# servo_cape.net
KiCad netlist of a schematic drawn in EAGLE
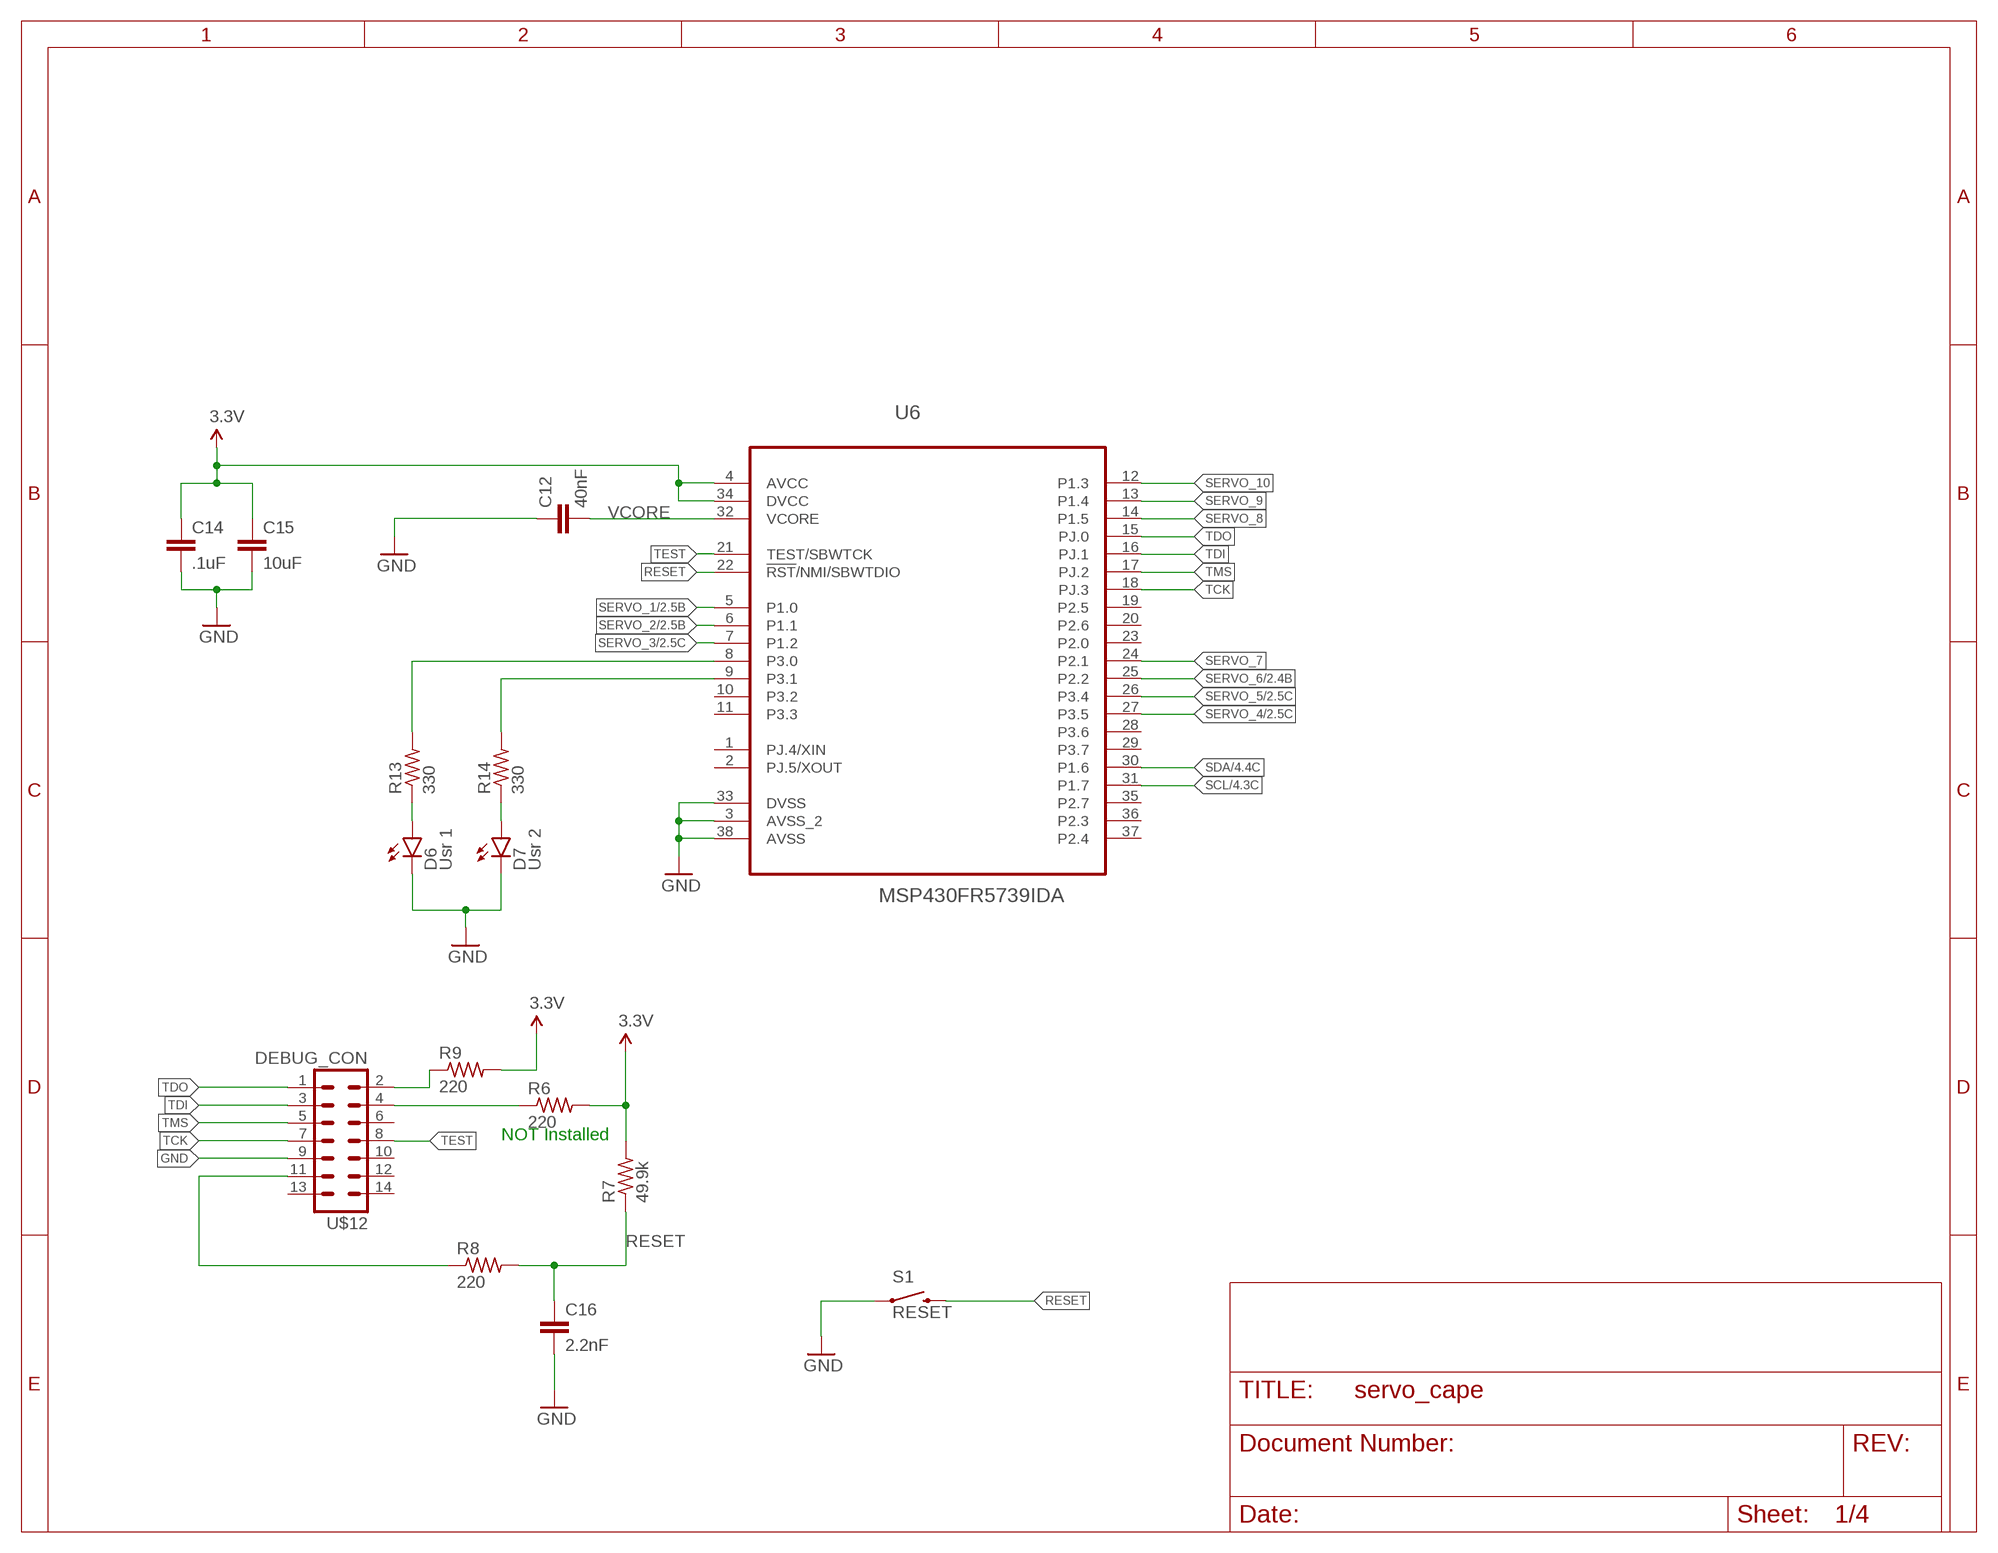
[diagram p0: schematic, sheet 1]
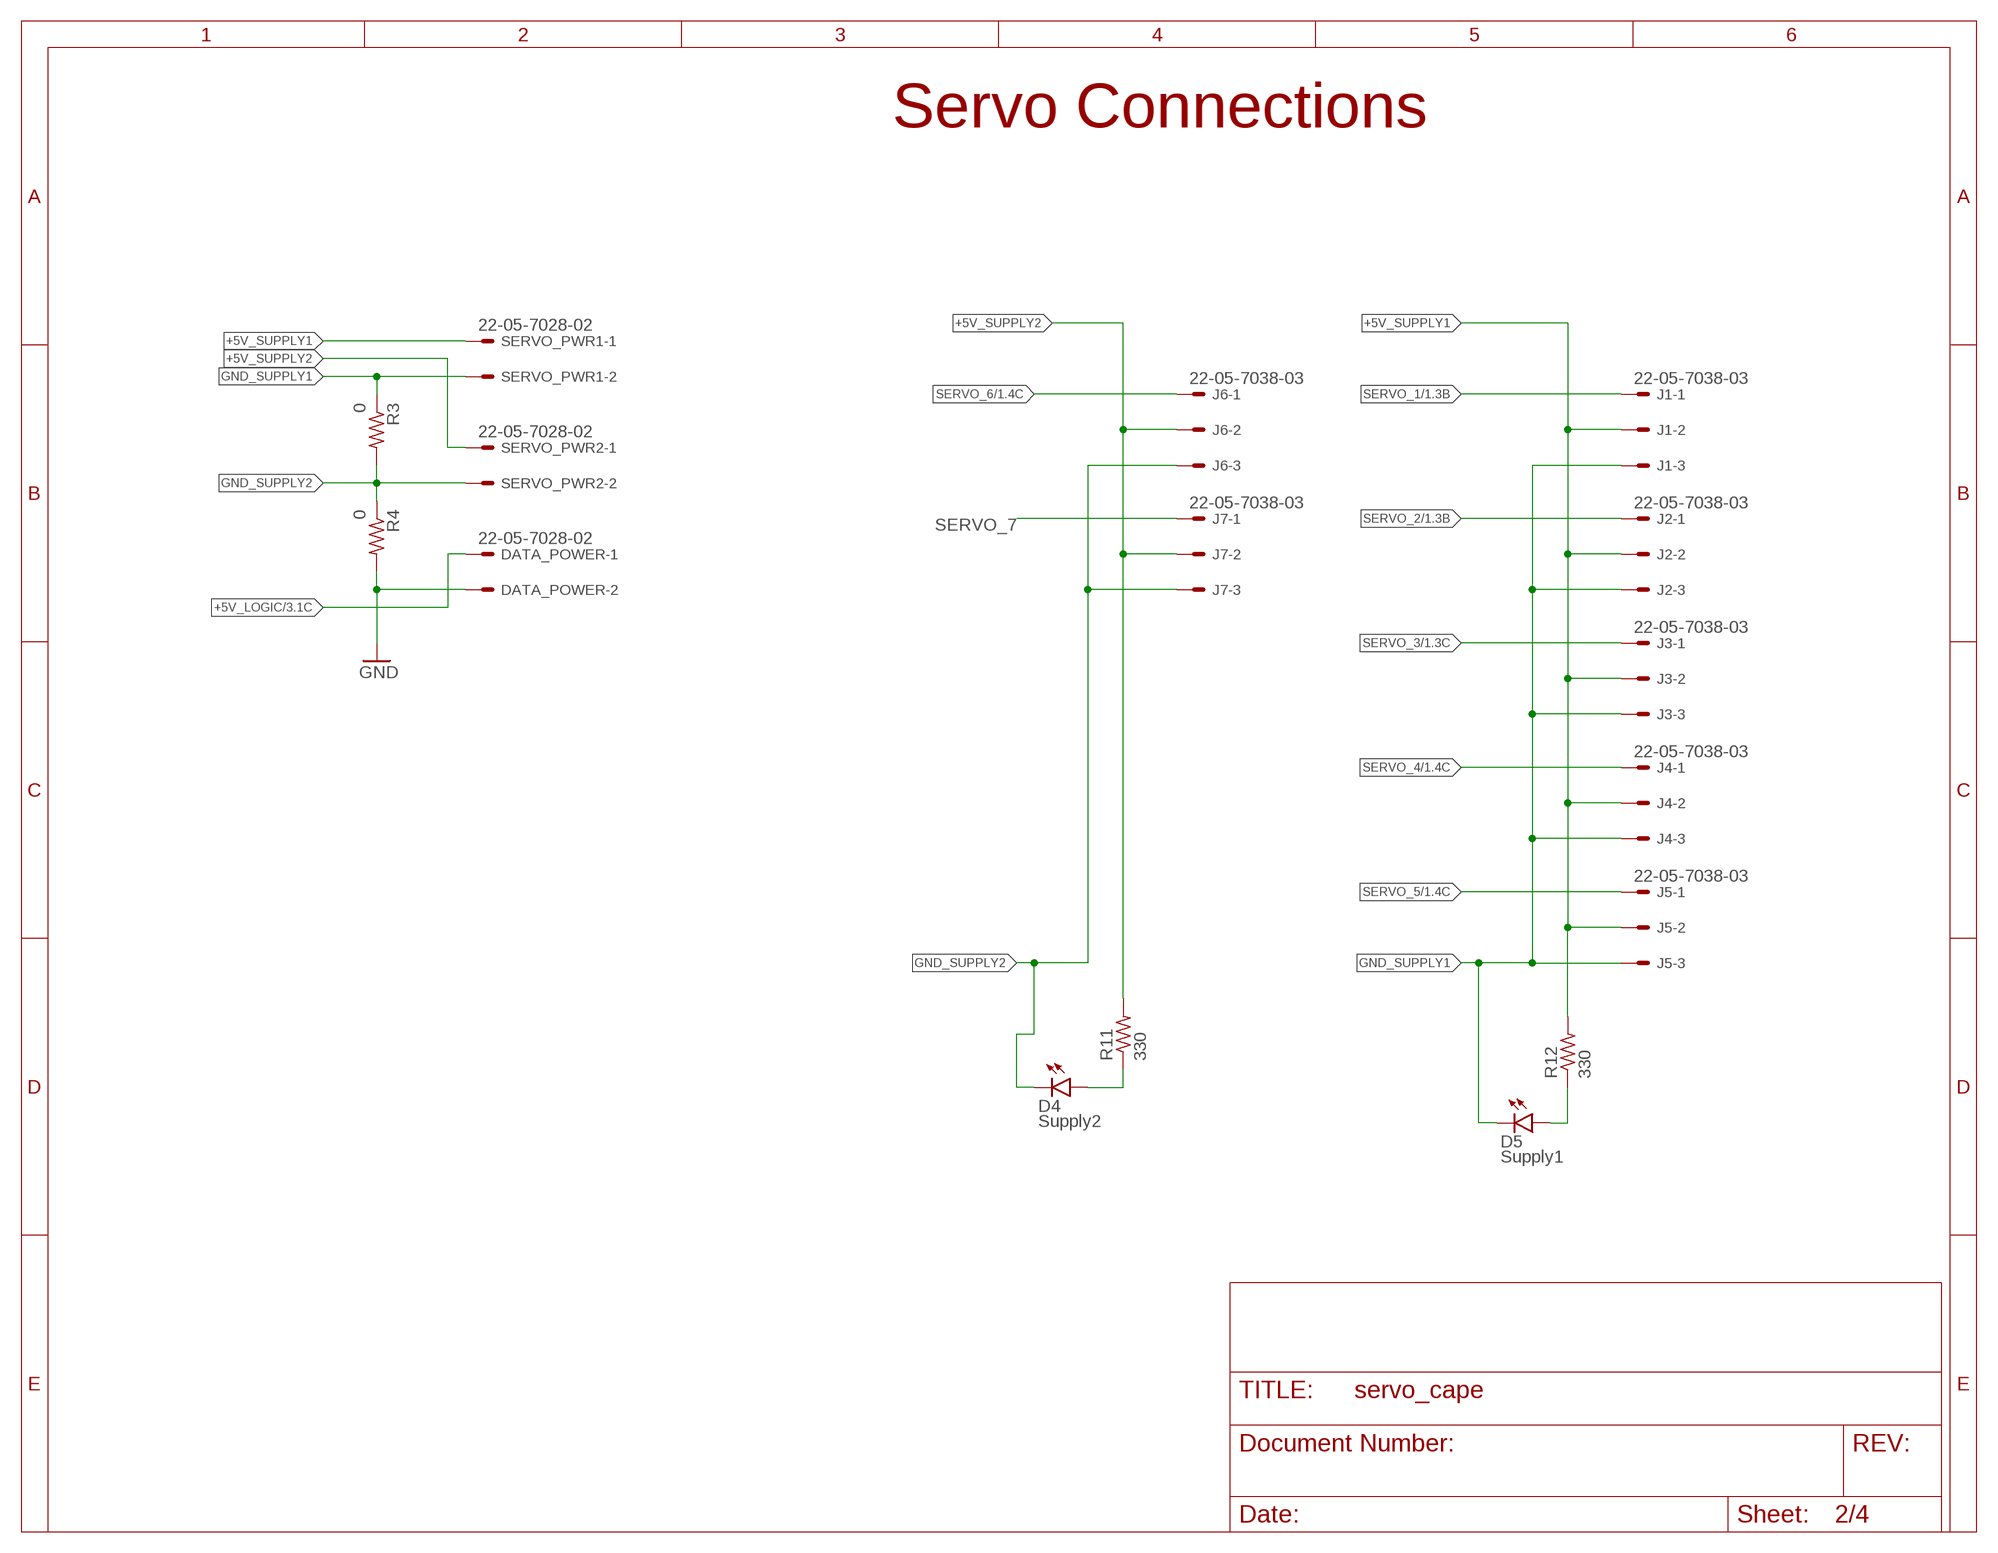
[diagram p1: schematic, sheet 2]
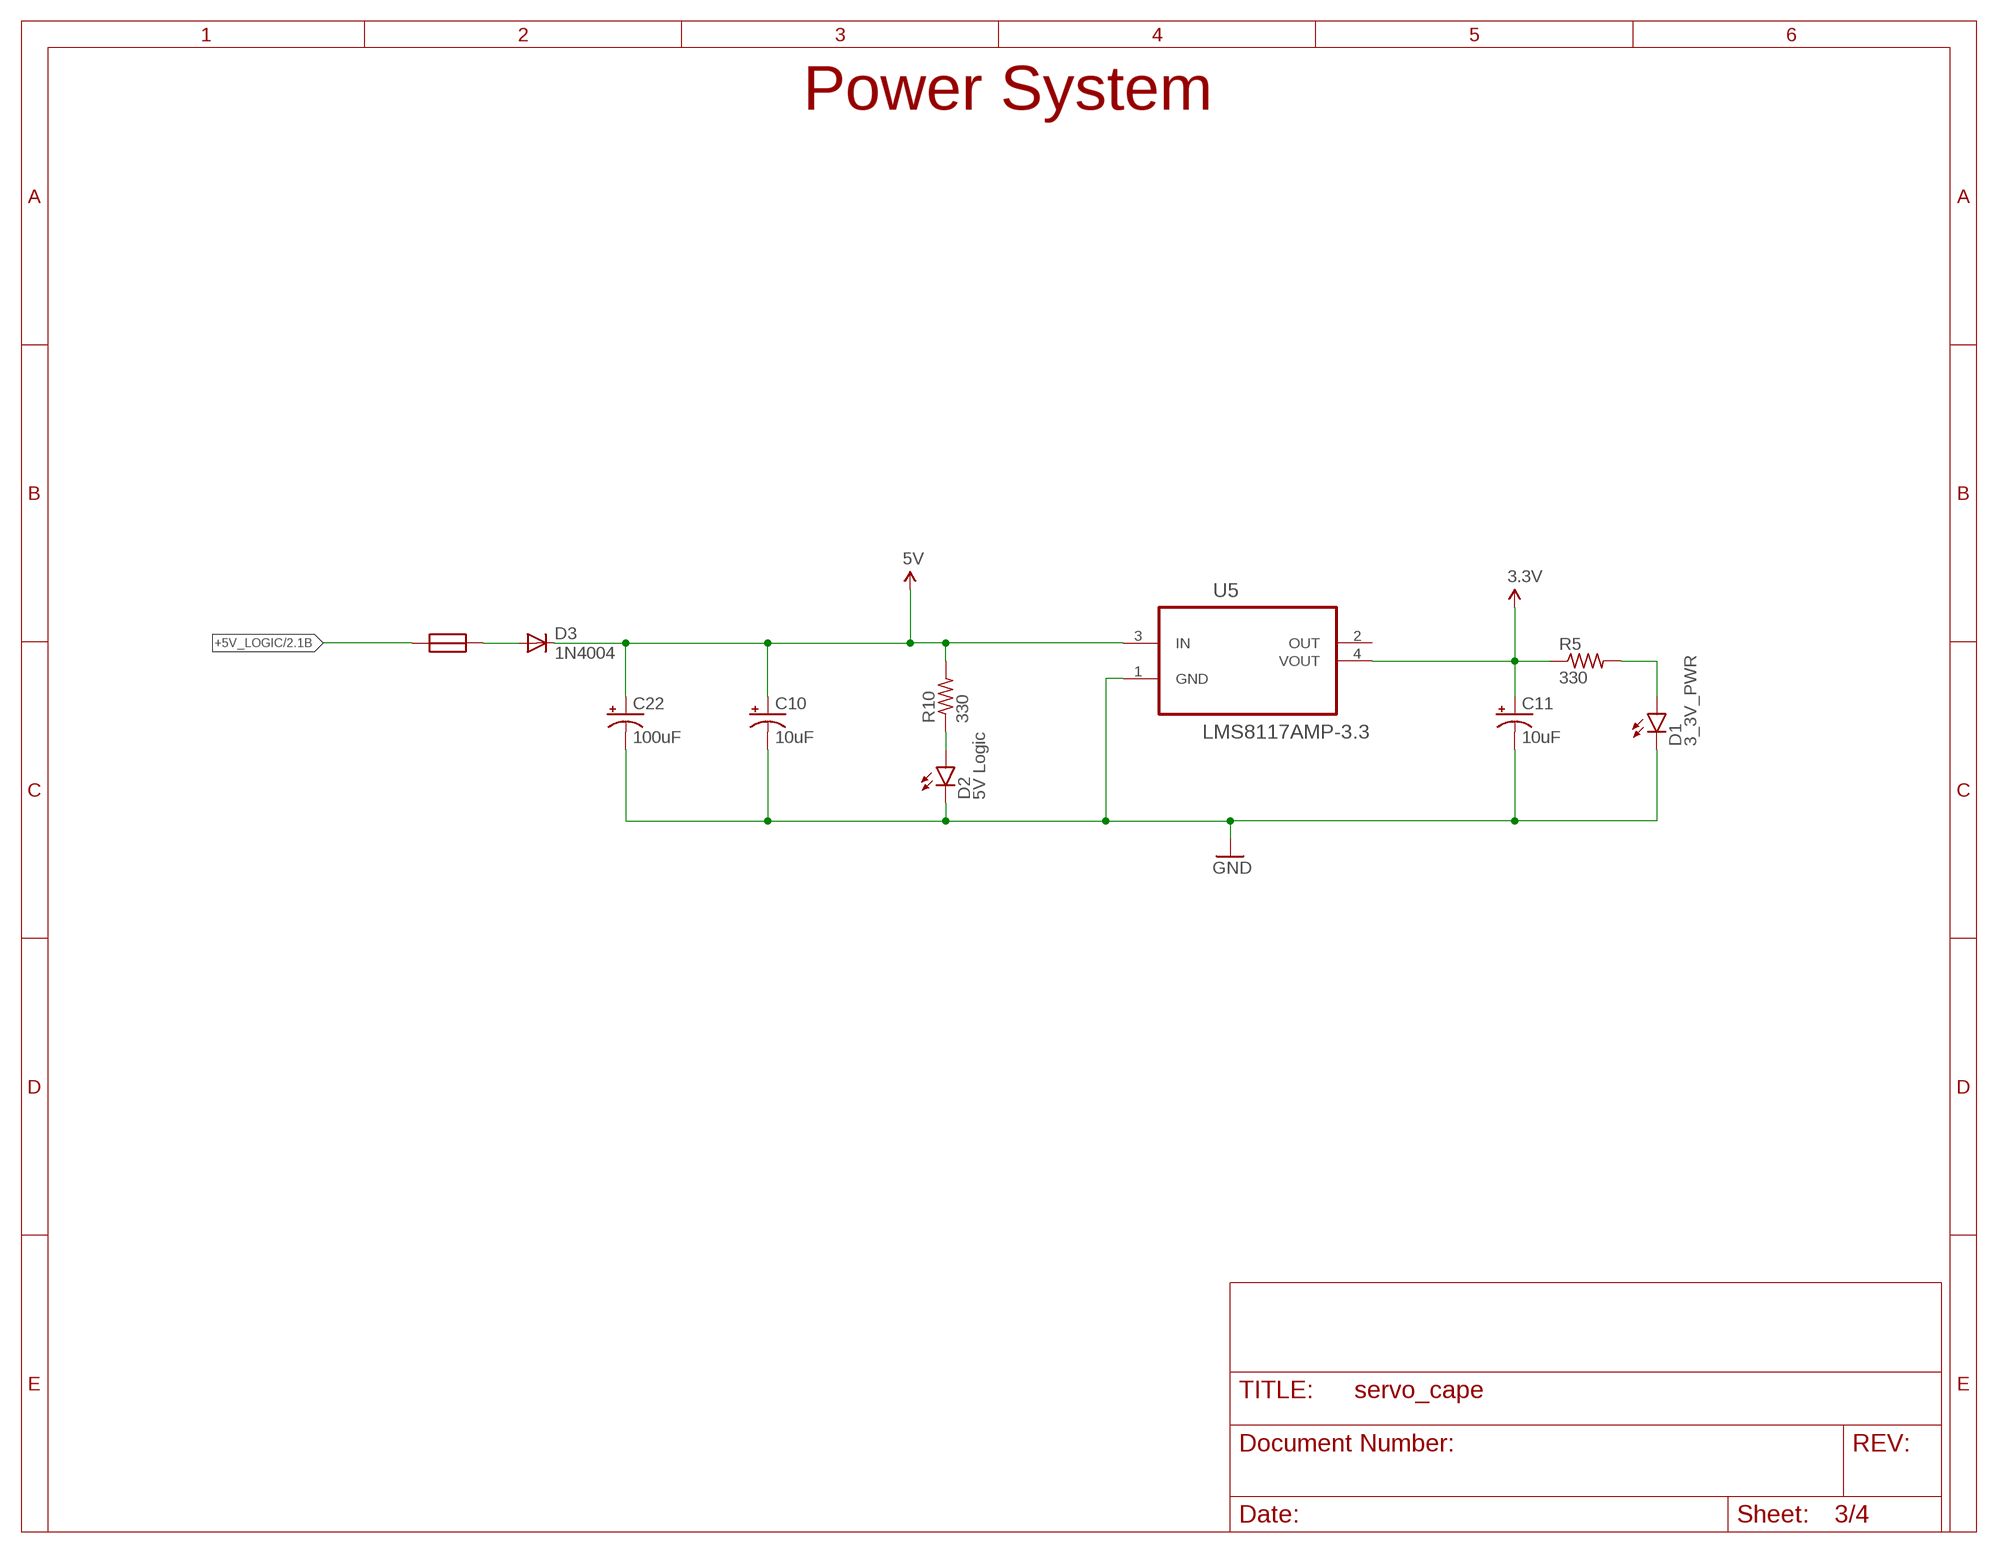
[diagram p2: schematic, sheet 3]
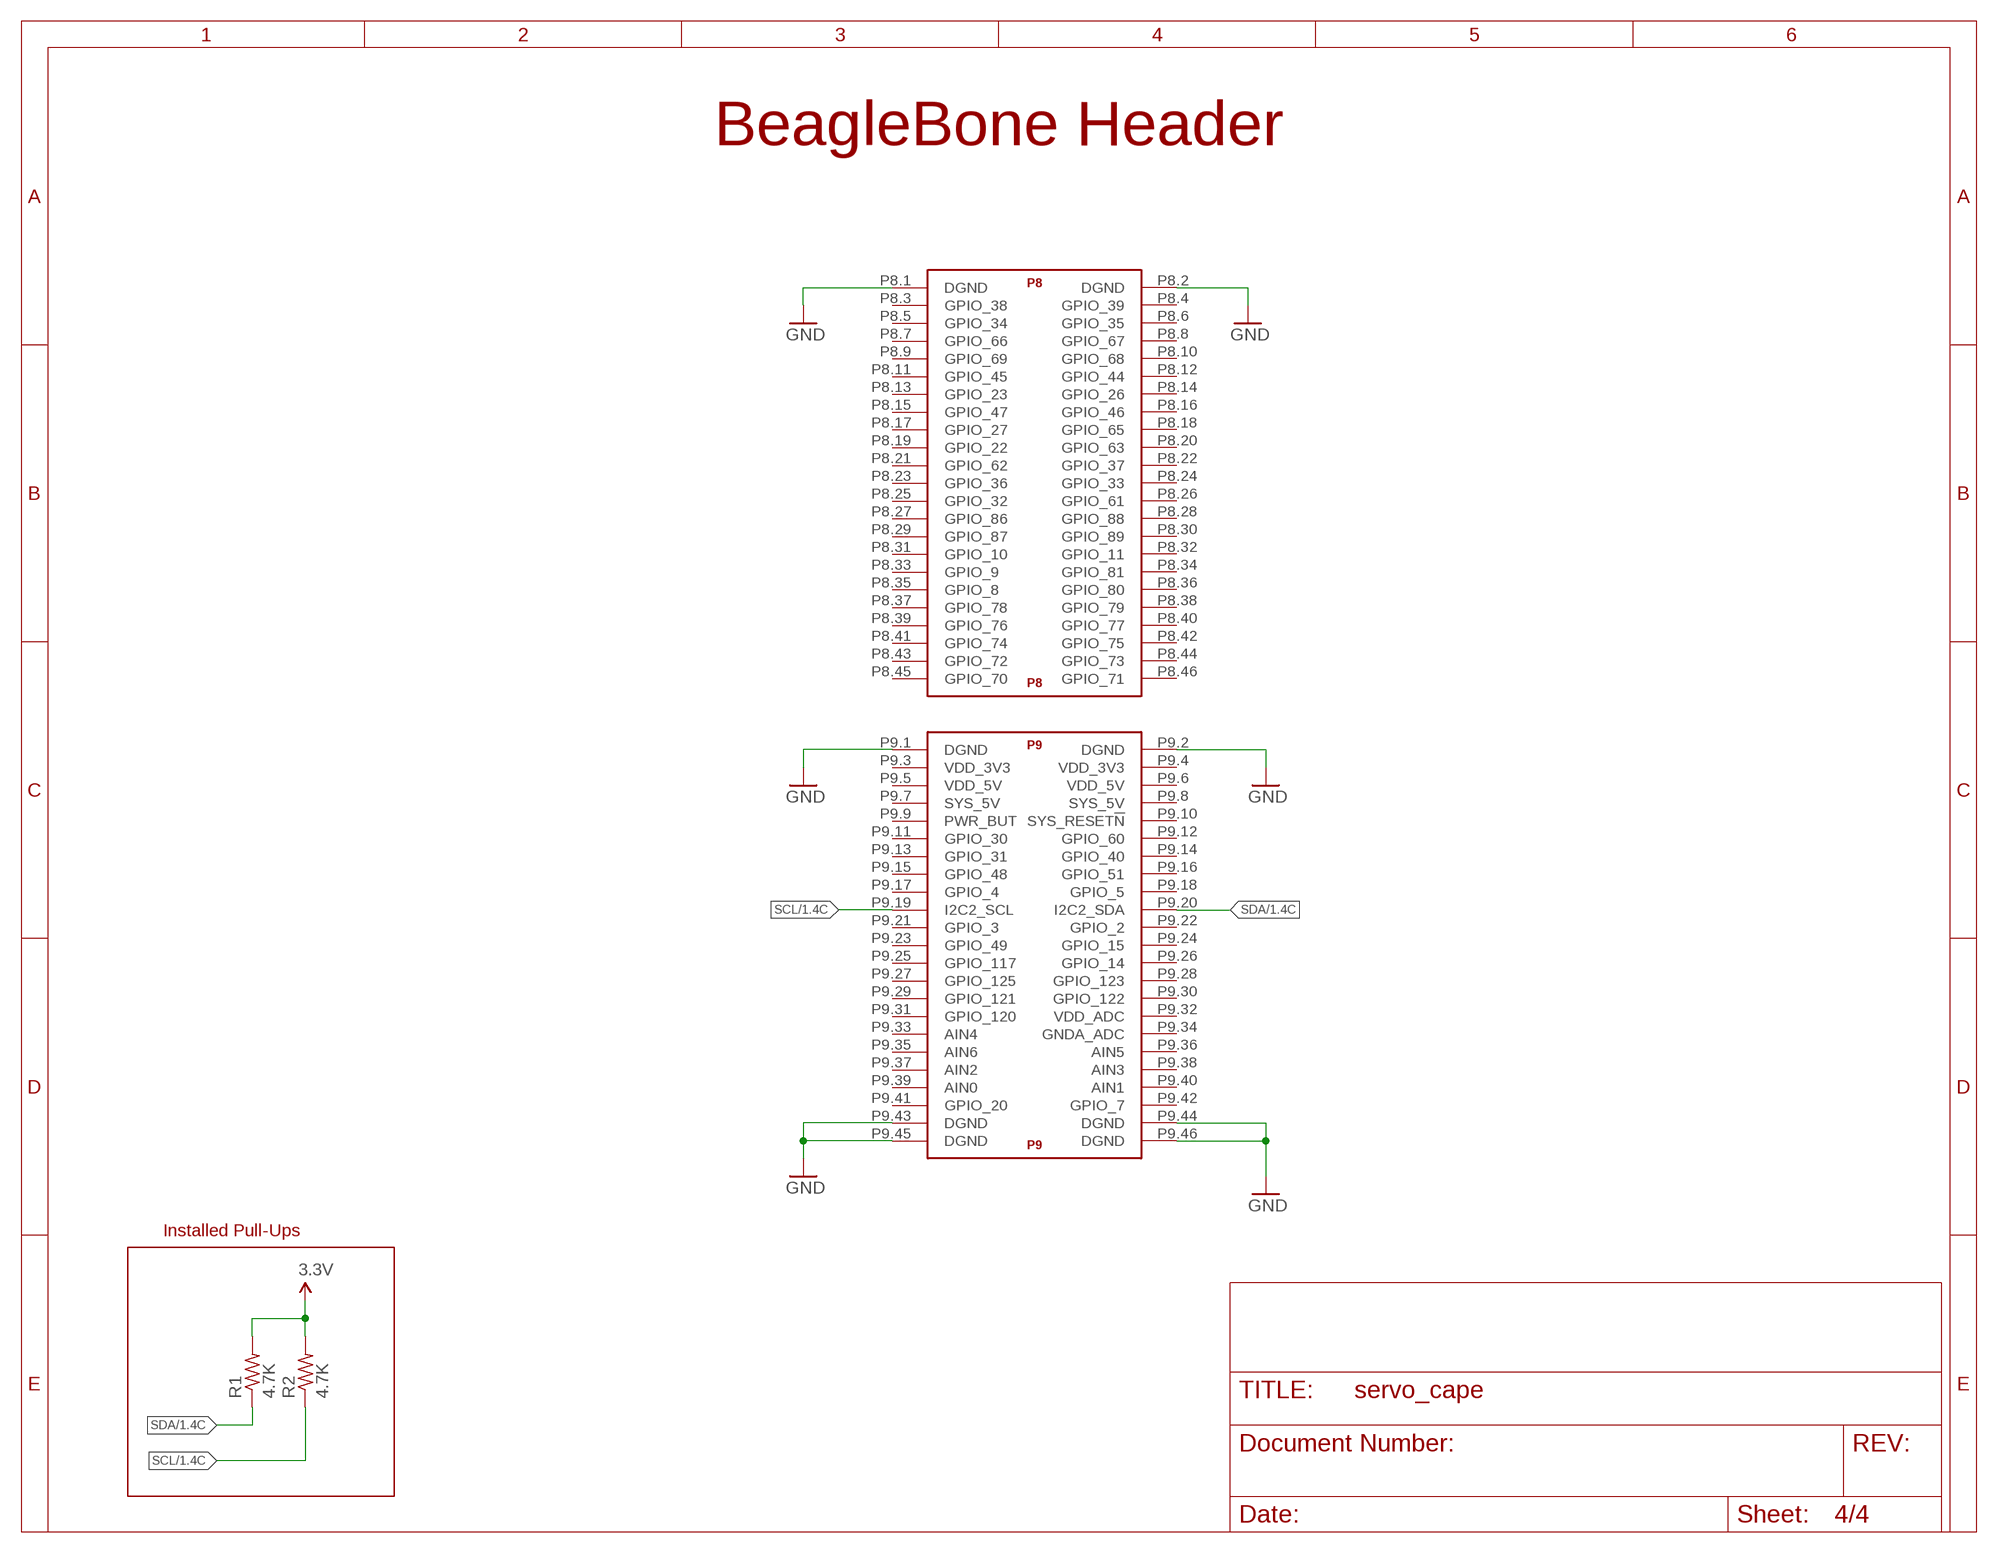
[diagram p3: schematic, sheet 4]

(export (version "E")
  (design (tool "Eeschema 10.0.6"))
  (components
    (comp (ref "D4")
      (value "Supply2")
      (footprint "eagle-import:FKIT-LED-1206")
      (libsource (lib "eagle-import") (part "LED-FKIT-1206"))
    )
    (comp (ref "D5")
      (value "Supply1")
      (footprint "eagle-import:FKIT-LED-1206")
      (libsource (lib "eagle-import") (part "LED-FKIT-1206"))
    )
    (comp (ref "DATA_POWER")
      (value "22-05-7028-02")
      (footprint "eagle-import:7395-02")
      (libsource (lib "eagle-import") (part "22-?-0205-7028"))
    )
    (comp (ref "J1")
      (value "22-05-7038-03")
      (footprint "eagle-import:7395-03")
      (libsource (lib "eagle-import") (part "22-?-0305-7038"))
    )
    (comp (ref "J2")
      (value "22-05-7038-03")
      (footprint "eagle-import:7395-03")
      (libsource (lib "eagle-import") (part "22-?-0305-7038"))
    )
    (comp (ref "J3")
      (value "22-05-7038-03")
      (footprint "eagle-import:7395-03")
      (libsource (lib "eagle-import") (part "22-?-0305-7038"))
    )
    (comp (ref "J4")
      (value "22-05-7038-03")
      (footprint "eagle-import:7395-03")
      (libsource (lib "eagle-import") (part "22-?-0305-7038"))
    )
    (comp (ref "J5")
      (value "22-05-7038-03")
      (footprint "eagle-import:7395-03")
      (libsource (lib "eagle-import") (part "22-?-0305-7038"))
    )
    (comp (ref "J6")
      (value "22-05-7038-03")
      (footprint "eagle-import:7395-03")
      (libsource (lib "eagle-import") (part "22-?-0305-7038"))
    )
    (comp (ref "J7")
      (value "22-05-7038-03")
      (footprint "eagle-import:7395-03")
      (libsource (lib "eagle-import") (part "22-?-0305-7038"))
    )
    (comp (ref "R3")
      (value "0")
      (footprint "eagle-import:R0805W")
      (libsource (lib "eagle-import") (part "R-US_R0805W"))
    )
    (comp (ref "R4")
      (value "0")
      (footprint "eagle-import:R0805W")
      (libsource (lib "eagle-import") (part "R-US_R0805W"))
    )
    (comp (ref "R11")
      (value "330")
      (footprint "eagle-import:R0805W")
      (libsource (lib "eagle-import") (part "R-US_R0805W"))
    )
    (comp (ref "R12")
      (value "330")
      (footprint "eagle-import:R0805W")
      (libsource (lib "eagle-import") (part "R-US_R0805W"))
    )
    (comp (ref "SERVO_PWR1")
      (value "22-05-7028-02")
      (footprint "eagle-import:7395-02")
      (libsource (lib "eagle-import") (part "22-?-0205-7028"))
    )
    (comp (ref "SERVO_PWR2")
      (value "22-05-7028-02")
      (footprint "eagle-import:7395-02")
      (libsource (lib "eagle-import") (part "22-?-0205-7028"))
    )
    (comp (ref "R1")
      (value "4.7K")
      (footprint "eagle-import:R0805W")
      (libsource (lib "eagle-import") (part "R-US_R0805W"))
    )
    (comp (ref "R2")
      (value "4.7K")
      (footprint "eagle-import:R0805W")
      (libsource (lib "eagle-import") (part "R-US_R0805W"))
    )
    (comp (ref "U$1")
      (value "BEAGLE_BONE_BLACK_CAPE")
      (footprint "eagle-import:BEAGLE_BONE_BLACK_CAPE")
      (libsource (lib "eagle-import") (part "BEAGLE_BONE_BLACK_CAPE"))
    )
    (comp (ref "C10")
      (value "10uF")
      (footprint "eagle-import:EIA3216")
      (libsource (lib "eagle-import") (part "10UF-16V-10%(TANT)"))
    )
    (comp (ref "C11")
      (value "10uF")
      (footprint "eagle-import:EIA3216")
      (libsource (lib "eagle-import") (part "10UF-16V-10%(TANT)"))
    )
    (comp (ref "C22")
      (value "100uF")
      (footprint "eagle-import:EIA7343")
      (libsource (lib "eagle-import") (part "100UF-10V-10%(TANT)"))
    )
    (comp (ref "D1")
      (value "3_3V_PWR")
      (footprint "eagle-import:FKIT-LED-1206")
      (libsource (lib "eagle-import") (part "LED-FKIT-1206"))
    )
    (comp (ref "D2")
      (value "5V Logic")
      (footprint "eagle-import:FKIT-LED-1206")
      (libsource (lib "eagle-import") (part "LED-FKIT-1206"))
    )
    (comp (ref "D3")
      (value "1N4004")
      (footprint "eagle-import:DO41-10")
      (libsource (lib "eagle-import") (part "1N4004"))
    )
    (comp (ref "R5")
      (value "330")
      (footprint "eagle-import:R0805W")
      (libsource (lib "eagle-import") (part "R-US_R0805W"))
    )
    (comp (ref "R10")
      (value "330")
      (footprint "eagle-import:R0805W")
      (libsource (lib "eagle-import") (part "R-US_R0805W"))
    )
    (comp (ref "U$3")
      (value "NANO_FUSE")
      (footprint "eagle-import:NANO_FUSE")
      (libsource (lib "eagle-import") (part "NANO_FUSE"))
    )
    (comp (ref "U5")
      (value "LMS8117AMP-3.3")
      (footprint "eagle-import:SOT230P696X180-4N")
      (libsource (lib "eagle-import") (part "LMS8117AMP-3.3"))
    )
    (comp (ref "C12")
      (value "40nF")
      (footprint "eagle-import:0805")
      (libsource (lib "eagle-import") (part "CAP0805"))
    )
    (comp (ref "C14")
      (value ".1uF")
      (footprint "eagle-import:0805")
      (libsource (lib "eagle-import") (part "CAP0805"))
    )
    (comp (ref "C15")
      (value "10uF")
      (footprint "eagle-import:0805")
      (libsource (lib "eagle-import") (part "CAP0805"))
    )
    (comp (ref "C16")
      (value "2.2nF")
      (footprint "eagle-import:0805")
      (libsource (lib "eagle-import") (part "CAP0805"))
    )
    (comp (ref "D6")
      (value "Usr 1")
      (footprint "eagle-import:FKIT-LED-1206")
      (libsource (lib "eagle-import") (part "LED-FKIT-1206"))
    )
    (comp (ref "D7")
      (value "Usr 2")
      (footprint "eagle-import:FKIT-LED-1206")
      (libsource (lib "eagle-import") (part "LED-FKIT-1206"))
    )
    (comp (ref "R6")
      (value "220")
      (footprint "eagle-import:R0805W")
      (libsource (lib "eagle-import") (part "R-US_R0805W"))
    )
    (comp (ref "R7")
      (value "49.9k")
      (footprint "eagle-import:R0805W")
      (libsource (lib "eagle-import") (part "R-US_R0805W"))
    )
    (comp (ref "R8")
      (value "220")
      (footprint "eagle-import:R0805W")
      (libsource (lib "eagle-import") (part "R-US_R0805W"))
    )
    (comp (ref "R9")
      (value "220")
      (footprint "eagle-import:R0805W")
      (libsource (lib "eagle-import") (part "R-US_R0805W"))
    )
    (comp (ref "R13")
      (value "330")
      (footprint "eagle-import:R0805W")
      (libsource (lib "eagle-import") (part "R-US_R0805W"))
    )
    (comp (ref "R14")
      (value "330")
      (footprint "eagle-import:R0805W")
      (libsource (lib "eagle-import") (part "R-US_R0805W"))
    )
    (comp (ref "S1")
      (value "RESET")
      (footprint "eagle-import:TACTILE_SWITCH_TALL")
      (libsource (lib "eagle-import") (part "SWITCH-MOMENTARY-2SMD-4"))
    )
    (comp (ref "U$12")
      (value "DEBUG_CON")
      (footprint "eagle-import:DEBUG_SM")
      (libsource (lib "eagle-import") (part "DEBUG_CON"))
    )
    (comp (ref "U6")
      (value "MSP430FR5739IDA")
      (footprint "eagle-import:SOP65P810X120-38N")
      (fields (field (name "MPN") "MSP430FR5739IDA "))
      (libsource (lib "eagle-import") (part "MSP430FR5739IDA"))
    )
  )
  (nets
    (net (code "1") (name "+5V_LOGIC") (class "Default")
      (node (ref "DATA_POWER") (pin "1") (pinfunction "S_1") (pintype "passive"))
      (node (ref "U$3") (pin "1") (pinfunction "1_1") (pintype "bidirectional"))
    )
    (net (code "2") (name "+5V_SUPPLY1") (class "Default")
      (node (ref "J1") (pin "2") (pinfunction "S_2") (pintype "passive"))
      (node (ref "J2") (pin "2") (pinfunction "S_2") (pintype "passive"))
      (node (ref "J3") (pin "2") (pinfunction "S_2") (pintype "passive"))
      (node (ref "J4") (pin "2") (pinfunction "S_2") (pintype "passive"))
      (node (ref "J5") (pin "2") (pinfunction "S_2") (pintype "passive"))
      (node (ref "R12") (pin "2") (pinfunction "2_2") (pintype "passive"))
      (node (ref "SERVO_PWR1") (pin "1") (pinfunction "S_1") (pintype "passive"))
    )
    (net (code "3") (name "+5V_SUPPLY2") (class "Default")
      (node (ref "J6") (pin "2") (pinfunction "S_2") (pintype "passive"))
      (node (ref "J7") (pin "2") (pinfunction "S_2") (pintype "passive"))
      (node (ref "R11") (pin "2") (pinfunction "2_2") (pintype "passive"))
      (node (ref "SERVO_PWR2") (pin "1") (pinfunction "S_1") (pintype "passive"))
    )
    (net (code "4") (name "3.3V") (class "Default")
      (node (ref "C11") (pin "A") (pinfunction "+_A") (pintype "passive"))
      (node (ref "C14") (pin "1") (pinfunction "1_1") (pintype "passive"))
      (node (ref "C15") (pin "1") (pinfunction "1_1") (pintype "passive"))
      (node (ref "R1") (pin "2") (pinfunction "2_2") (pintype "passive"))
      (node (ref "R2") (pin "2") (pinfunction "2_2") (pintype "passive"))
      (node (ref "R5") (pin "1") (pinfunction "1_1") (pintype "passive"))
      (node (ref "R6") (pin "2") (pinfunction "2_2") (pintype "passive"))
      (node (ref "R7") (pin "2") (pinfunction "2_2") (pintype "passive"))
      (node (ref "R9") (pin "2") (pinfunction "2_2") (pintype "passive"))
      (node (ref "U5") (pin "4") (pinfunction "VOUT_4") (pintype "power_in"))
      (node (ref "U6") (pin "34") (pinfunction "DVCC_34") (pintype "power_in"))
      (node (ref "U6") (pin "4") (pinfunction "AVCC_4") (pintype "power_in"))
    )
    (net (code "5") (name "5V") (class "Default")
      (node (ref "C10") (pin "A") (pinfunction "+_A") (pintype "passive"))
      (node (ref "C22") (pin "A") (pinfunction "+_A") (pintype "passive"))
      (node (ref "D3") (pin "C") (pinfunction "C_C") (pintype "passive"))
      (node (ref "R10") (pin "2") (pinfunction "2_2") (pintype "passive"))
      (node (ref "U5") (pin "3") (pinfunction "IN_3") (pintype "power_in"))
    )
    (net (code "6") (name "GND") (class "Default")
      (node (ref "C10") (pin "C") (pinfunction "-_C") (pintype "passive"))
      (node (ref "C11") (pin "C") (pinfunction "-_C") (pintype "passive"))
      (node (ref "C12") (pin "1") (pinfunction "1_1") (pintype "passive"))
      (node (ref "C14") (pin "2") (pinfunction "2_2") (pintype "passive"))
      (node (ref "C15") (pin "2") (pinfunction "2_2") (pintype "passive"))
      (node (ref "C16") (pin "2") (pinfunction "2_2") (pintype "passive"))
      (node (ref "C22") (pin "C") (pinfunction "-_C") (pintype "passive"))
      (node (ref "D1") (pin "C") (pinfunction "C_C") (pintype "passive"))
      (node (ref "D2") (pin "C") (pinfunction "C_C") (pintype "passive"))
      (node (ref "D6") (pin "C") (pinfunction "C_C") (pintype "passive"))
      (node (ref "D7") (pin "C") (pinfunction "C_C") (pintype "passive"))
      (node (ref "DATA_POWER") (pin "2") (pinfunction "S_2") (pintype "passive"))
      (node (ref "R4") (pin "2") (pinfunction "2_2") (pintype "passive"))
      (node (ref "S1") (pin "A2") (pinfunction "1_A2") (pintype "passive"))
      (node (ref "U$1") (pin "P8.1") (pinfunction "DGND_P8.1") (pintype "bidirectional"))
      (node (ref "U$1") (pin "P8.2") (pinfunction "DGND_P8.2") (pintype "bidirectional"))
      (node (ref "U$1") (pin "P9.1") (pinfunction "DGND_P9.1") (pintype "bidirectional"))
      (node (ref "U$1") (pin "P9.2") (pinfunction "DGND_P9.2") (pintype "bidirectional"))
      (node (ref "U$1") (pin "P9.43") (pinfunction "DGND_P9.43") (pintype "bidirectional"))
      (node (ref "U$1") (pin "P9.44") (pinfunction "DGND_P9.44") (pintype "bidirectional"))
      (node (ref "U$1") (pin "P9.45") (pinfunction "DGND_P9.45") (pintype "bidirectional"))
      (node (ref "U$1") (pin "P9.46") (pinfunction "DGND_P9.46") (pintype "bidirectional"))
      (node (ref "U$12") (pin "9") (pinfunction "9_9") (pintype "passive"))
      (node (ref "U5") (pin "1") (pinfunction "GND_1") (pintype "passive"))
      (node (ref "U6") (pin "3") (pinfunction "AVSS_2_3") (pintype "passive"))
      (node (ref "U6") (pin "33") (pinfunction "DVSS_33") (pintype "passive"))
      (node (ref "U6") (pin "38") (pinfunction "AVSS_38") (pintype "passive"))
    )
    (net (code "7") (name "GND_SUPPLY1") (class "Default")
      (node (ref "D5") (pin "C") (pinfunction "C_C") (pintype "passive"))
      (node (ref "J1") (pin "3") (pinfunction "S_3") (pintype "passive"))
      (node (ref "J2") (pin "3") (pinfunction "S_3") (pintype "passive"))
      (node (ref "J3") (pin "3") (pinfunction "S_3") (pintype "passive"))
      (node (ref "J4") (pin "3") (pinfunction "S_3") (pintype "passive"))
      (node (ref "J5") (pin "3") (pinfunction "S_3") (pintype "passive"))
      (node (ref "R3") (pin "1") (pinfunction "1_1") (pintype "passive"))
      (node (ref "SERVO_PWR1") (pin "2") (pinfunction "S_2") (pintype "passive"))
    )
    (net (code "8") (name "GND_SUPPLY2") (class "Default")
      (node (ref "D4") (pin "C") (pinfunction "C_C") (pintype "passive"))
      (node (ref "J6") (pin "3") (pinfunction "S_3") (pintype "passive"))
      (node (ref "J7") (pin "3") (pinfunction "S_3") (pintype "passive"))
      (node (ref "R3") (pin "2") (pinfunction "2_2") (pintype "passive"))
      (node (ref "R4") (pin "1") (pinfunction "1_1") (pintype "passive"))
      (node (ref "SERVO_PWR2") (pin "2") (pinfunction "S_2") (pintype "passive"))
    )
    (net (code "9") (name "Net-(D1-PadA)") (class "Default")
      (node (ref "D1") (pin "A") (pinfunction "A_A") (pintype "passive"))
      (node (ref "R5") (pin "2") (pinfunction "2_2") (pintype "passive"))
    )
    (net (code "10") (name "Net-(D2-PadA)") (class "Default")
      (node (ref "D2") (pin "A") (pinfunction "A_A") (pintype "passive"))
      (node (ref "R10") (pin "1") (pinfunction "1_1") (pintype "passive"))
    )
    (net (code "11") (name "Net-(D3-PadA)") (class "Default")
      (node (ref "D3") (pin "A") (pinfunction "A_A") (pintype "passive"))
      (node (ref "U$3") (pin "2") (pinfunction "2_2") (pintype "bidirectional"))
    )
    (net (code "12") (name "Net-(D4-PadA)") (class "Default")
      (node (ref "D4") (pin "A") (pinfunction "A_A") (pintype "passive"))
      (node (ref "R11") (pin "1") (pinfunction "1_1") (pintype "passive"))
    )
    (net (code "13") (name "Net-(D5-PadA)") (class "Default")
      (node (ref "D5") (pin "A") (pinfunction "A_A") (pintype "passive"))
      (node (ref "R12") (pin "1") (pinfunction "1_1") (pintype "passive"))
    )
    (net (code "14") (name "Net-(D6-PadA)") (class "Default")
      (node (ref "D6") (pin "A") (pinfunction "A_A") (pintype "passive"))
      (node (ref "R13") (pin "1") (pinfunction "1_1") (pintype "passive"))
    )
    (net (code "15") (name "Net-(D7-PadA)") (class "Default")
      (node (ref "D7") (pin "A") (pinfunction "A_A") (pintype "passive"))
      (node (ref "R14") (pin "1") (pinfunction "1_1") (pintype "passive"))
    )
    (net (code "16") (name "Net-(R6-Pad1)") (class "Default")
      (node (ref "R6") (pin "1") (pinfunction "1_1") (pintype "passive"))
      (node (ref "U$12") (pin "4") (pinfunction "4_4") (pintype "passive"))
    )
    (net (code "17") (name "Net-(R8-Pad1)") (class "Default")
      (node (ref "R8") (pin "1") (pinfunction "1_1") (pintype "passive"))
      (node (ref "U$12") (pin "11") (pinfunction "11_11") (pintype "passive"))
    )
    (net (code "18") (name "Net-(R9-Pad1)") (class "Default")
      (node (ref "R9") (pin "1") (pinfunction "1_1") (pintype "passive"))
      (node (ref "U$12") (pin "2") (pinfunction "2_2") (pintype "passive"))
    )
    (net (code "19") (name "Net-(U6-P3.0)") (class "Default")
      (node (ref "R13") (pin "2") (pinfunction "2_2") (pintype "passive"))
      (node (ref "U6") (pin "8") (pinfunction "P3.0_8") (pintype "bidirectional"))
    )
    (net (code "20") (name "Net-(U6-P3.1)") (class "Default")
      (node (ref "R14") (pin "2") (pinfunction "2_2") (pintype "passive"))
      (node (ref "U6") (pin "9") (pinfunction "P3.1_9") (pintype "bidirectional"))
    )
    (net (code "21") (name "RESET") (class "Default")
      (node (ref "C16") (pin "1") (pinfunction "1_1") (pintype "passive"))
      (node (ref "R7") (pin "1") (pinfunction "1_1") (pintype "passive"))
      (node (ref "R8") (pin "2") (pinfunction "2_2") (pintype "passive"))
      (node (ref "S1") (pin "B2") (pinfunction "2_B2") (pintype "passive"))
      (node (ref "U6") (pin "22") (pinfunction "~{RST}/NMI/SBWTDIO_22") (pintype "input"))
    )
    (net (code "22") (name "SCL") (class "Default")
      (node (ref "R2") (pin "1") (pinfunction "1_1") (pintype "passive"))
      (node (ref "U$1") (pin "P9.19") (pinfunction "I2C2_SCL_P9.19") (pintype "bidirectional"))
      (node (ref "U6") (pin "31") (pinfunction "P1.7_31") (pintype "bidirectional"))
    )
    (net (code "23") (name "SDA") (class "Default")
      (node (ref "R1") (pin "1") (pinfunction "1_1") (pintype "passive"))
      (node (ref "U$1") (pin "P9.20") (pinfunction "I2C2_SDA_P9.20") (pintype "bidirectional"))
      (node (ref "U6") (pin "30") (pinfunction "P1.6_30") (pintype "bidirectional"))
    )
    (net (code "24") (name "SERVO_1") (class "Default")
      (node (ref "J1") (pin "1") (pinfunction "S_1") (pintype "passive"))
      (node (ref "U6") (pin "5") (pinfunction "P1.0_5") (pintype "bidirectional"))
    )
    (net (code "25") (name "SERVO_2") (class "Default")
      (node (ref "J2") (pin "1") (pinfunction "S_1") (pintype "passive"))
      (node (ref "U6") (pin "6") (pinfunction "P1.1_6") (pintype "bidirectional"))
    )
    (net (code "26") (name "SERVO_3") (class "Default")
      (node (ref "J3") (pin "1") (pinfunction "S_1") (pintype "passive"))
      (node (ref "U6") (pin "7") (pinfunction "P1.2_7") (pintype "bidirectional"))
    )
    (net (code "27") (name "SERVO_4") (class "Default")
      (node (ref "J4") (pin "1") (pinfunction "S_1") (pintype "passive"))
      (node (ref "U6") (pin "27") (pinfunction "P3.5_27") (pintype "bidirectional"))
    )
    (net (code "28") (name "SERVO_5") (class "Default")
      (node (ref "J5") (pin "1") (pinfunction "S_1") (pintype "passive"))
      (node (ref "U6") (pin "26") (pinfunction "P3.4_26") (pintype "bidirectional"))
    )
    (net (code "29") (name "SERVO_6") (class "Default")
      (node (ref "J6") (pin "1") (pinfunction "S_1") (pintype "passive"))
      (node (ref "U6") (pin "25") (pinfunction "P2.2_25") (pintype "bidirectional"))
    )
    (net (code "30") (name "SERVO_7") (class "Default")
      (node (ref "J7") (pin "1") (pinfunction "S_1") (pintype "passive"))
      (node (ref "U6") (pin "24") (pinfunction "P2.1_24") (pintype "bidirectional"))
    )
    (net (code "31") (name "SERVO_8") (class "Default")
      (node (ref "U6") (pin "14") (pinfunction "P1.5_14") (pintype "bidirectional"))
    )
    (net (code "32") (name "SERVO_9") (class "Default")
      (node (ref "U6") (pin "13") (pinfunction "P1.4_13") (pintype "bidirectional"))
    )
    (net (code "33") (name "SERVO_10") (class "Default")
      (node (ref "U6") (pin "12") (pinfunction "P1.3_12") (pintype "bidirectional"))
    )
    (net (code "34") (name "TCK") (class "Default")
      (node (ref "U$12") (pin "7") (pinfunction "7_7") (pintype "passive"))
      (node (ref "U6") (pin "18") (pinfunction "PJ.3_18") (pintype "bidirectional"))
    )
    (net (code "35") (name "TDI") (class "Default")
      (node (ref "U$12") (pin "3") (pinfunction "3_3") (pintype "passive"))
      (node (ref "U6") (pin "16") (pinfunction "PJ.1_16") (pintype "bidirectional"))
    )
    (net (code "36") (name "TDO") (class "Default")
      (node (ref "U$12") (pin "1") (pinfunction "1_1") (pintype "passive"))
      (node (ref "U6") (pin "15") (pinfunction "PJ.0_15") (pintype "bidirectional"))
    )
    (net (code "37") (name "TEST") (class "Default")
      (node (ref "U$12") (pin "8") (pinfunction "8_8") (pintype "passive"))
      (node (ref "U6") (pin "21") (pinfunction "TEST/SBWTCK_21") (pintype "input"))
    )
    (net (code "38") (name "TMS") (class "Default")
      (node (ref "U$12") (pin "5") (pinfunction "5_5") (pintype "passive"))
      (node (ref "U6") (pin "17") (pinfunction "PJ.2_17") (pintype "bidirectional"))
    )
    (net (code "39") (name "VCORE") (class "Default")
      (node (ref "C12") (pin "2") (pinfunction "2_2") (pintype "passive"))
      (node (ref "U6") (pin "32") (pinfunction "VCORE_32") (pintype "power_in"))
    )
    (net (code "40") (name "unconnected-(U$1A-GPIO_8-PadP8.35)") (class "Default")
      (node (ref "U$1") (pin "P8.35") (pinfunction "GPIO_8_P8.35") (pintype "bidirectional"))
    )
    (net (code "41") (name "unconnected-(U$1A-GPIO_9-PadP8.33)") (class "Default")
      (node (ref "U$1") (pin "P8.33") (pinfunction "GPIO_9_P8.33") (pintype "bidirectional"))
    )
    (net (code "42") (name "unconnected-(U$1A-GPIO_10-PadP8.31)") (class "Default")
      (node (ref "U$1") (pin "P8.31") (pinfunction "GPIO_10_P8.31") (pintype "bidirectional"))
    )
    (net (code "43") (name "unconnected-(U$1A-GPIO_11-PadP8.32)") (class "Default")
      (node (ref "U$1") (pin "P8.32") (pinfunction "GPIO_11_P8.32") (pintype "bidirectional"))
    )
    (net (code "44") (name "unconnected-(U$1A-GPIO_22-PadP8.19)") (class "Default")
      (node (ref "U$1") (pin "P8.19") (pinfunction "GPIO_22_P8.19") (pintype "bidirectional"))
    )
    (net (code "45") (name "unconnected-(U$1A-GPIO_23-PadP8.13)") (class "Default")
      (node (ref "U$1") (pin "P8.13") (pinfunction "GPIO_23_P8.13") (pintype "bidirectional"))
    )
    (net (code "46") (name "unconnected-(U$1A-GPIO_26-PadP8.14)") (class "Default")
      (node (ref "U$1") (pin "P8.14") (pinfunction "GPIO_26_P8.14") (pintype "bidirectional"))
    )
    (net (code "47") (name "unconnected-(U$1A-GPIO_27-PadP8.17)") (class "Default")
      (node (ref "U$1") (pin "P8.17") (pinfunction "GPIO_27_P8.17") (pintype "bidirectional"))
    )
    (net (code "48") (name "unconnected-(U$1A-GPIO_32-PadP8.25)") (class "Default")
      (node (ref "U$1") (pin "P8.25") (pinfunction "GPIO_32_P8.25") (pintype "bidirectional"))
    )
    (net (code "49") (name "unconnected-(U$1A-GPIO_33-PadP8.24)") (class "Default")
      (node (ref "U$1") (pin "P8.24") (pinfunction "GPIO_33_P8.24") (pintype "bidirectional"))
    )
    (net (code "50") (name "unconnected-(U$1A-GPIO_34-PadP8.5)") (class "Default")
      (node (ref "U$1") (pin "P8.5") (pinfunction "GPIO_34_P8.5") (pintype "bidirectional"))
    )
    (net (code "51") (name "unconnected-(U$1A-GPIO_35-PadP8.6)") (class "Default")
      (node (ref "U$1") (pin "P8.6") (pinfunction "GPIO_35_P8.6") (pintype "bidirectional"))
    )
    (net (code "52") (name "unconnected-(U$1A-GPIO_36-PadP8.23)") (class "Default")
      (node (ref "U$1") (pin "P8.23") (pinfunction "GPIO_36_P8.23") (pintype "bidirectional"))
    )
    (net (code "53") (name "unconnected-(U$1A-GPIO_37-PadP8.22)") (class "Default")
      (node (ref "U$1") (pin "P8.22") (pinfunction "GPIO_37_P8.22") (pintype "bidirectional"))
    )
    (net (code "54") (name "unconnected-(U$1A-GPIO_38-PadP8.3)") (class "Default")
      (node (ref "U$1") (pin "P8.3") (pinfunction "GPIO_38_P8.3") (pintype "bidirectional"))
    )
    (net (code "55") (name "unconnected-(U$1A-GPIO_39-PadP8.4)") (class "Default")
      (node (ref "U$1") (pin "P8.4") (pinfunction "GPIO_39_P8.4") (pintype "bidirectional"))
    )
    (net (code "56") (name "unconnected-(U$1A-GPIO_44-PadP8.12)") (class "Default")
      (node (ref "U$1") (pin "P8.12") (pinfunction "GPIO_44_P8.12") (pintype "bidirectional"))
    )
    (net (code "57") (name "unconnected-(U$1A-GPIO_45-PadP8.11)") (class "Default")
      (node (ref "U$1") (pin "P8.11") (pinfunction "GPIO_45_P8.11") (pintype "bidirectional"))
    )
    (net (code "58") (name "unconnected-(U$1A-GPIO_46-PadP8.16)") (class "Default")
      (node (ref "U$1") (pin "P8.16") (pinfunction "GPIO_46_P8.16") (pintype "bidirectional"))
    )
    (net (code "59") (name "unconnected-(U$1A-GPIO_47-PadP8.15)") (class "Default")
      (node (ref "U$1") (pin "P8.15") (pinfunction "GPIO_47_P8.15") (pintype "bidirectional"))
    )
    (net (code "60") (name "unconnected-(U$1A-GPIO_61-PadP8.26)") (class "Default")
      (node (ref "U$1") (pin "P8.26") (pinfunction "GPIO_61_P8.26") (pintype "bidirectional"))
    )
    (net (code "61") (name "unconnected-(U$1A-GPIO_62-PadP8.21)") (class "Default")
      (node (ref "U$1") (pin "P8.21") (pinfunction "GPIO_62_P8.21") (pintype "bidirectional"))
    )
    (net (code "62") (name "unconnected-(U$1A-GPIO_63-PadP8.20)") (class "Default")
      (node (ref "U$1") (pin "P8.20") (pinfunction "GPIO_63_P8.20") (pintype "bidirectional"))
    )
    (net (code "63") (name "unconnected-(U$1A-GPIO_65-PadP8.18)") (class "Default")
      (node (ref "U$1") (pin "P8.18") (pinfunction "GPIO_65_P8.18") (pintype "bidirectional"))
    )
    (net (code "64") (name "unconnected-(U$1A-GPIO_66-PadP8.7)") (class "Default")
      (node (ref "U$1") (pin "P8.7") (pinfunction "GPIO_66_P8.7") (pintype "bidirectional"))
    )
    (net (code "65") (name "unconnected-(U$1A-GPIO_67-PadP8.8)") (class "Default")
      (node (ref "U$1") (pin "P8.8") (pinfunction "GPIO_67_P8.8") (pintype "bidirectional"))
    )
    (net (code "66") (name "unconnected-(U$1A-GPIO_68-PadP8.10)") (class "Default")
      (node (ref "U$1") (pin "P8.10") (pinfunction "GPIO_68_P8.10") (pintype "bidirectional"))
    )
    (net (code "67") (name "unconnected-(U$1A-GPIO_69-PadP8.9)") (class "Default")
      (node (ref "U$1") (pin "P8.9") (pinfunction "GPIO_69_P8.9") (pintype "bidirectional"))
    )
    (net (code "68") (name "unconnected-(U$1A-GPIO_70-PadP8.45)") (class "Default")
      (node (ref "U$1") (pin "P8.45") (pinfunction "GPIO_70_P8.45") (pintype "bidirectional"))
    )
    (net (code "69") (name "unconnected-(U$1A-GPIO_71-PadP8.46)") (class "Default")
      (node (ref "U$1") (pin "P8.46") (pinfunction "GPIO_71_P8.46") (pintype "bidirectional"))
    )
    (net (code "70") (name "unconnected-(U$1A-GPIO_72-PadP8.43)") (class "Default")
      (node (ref "U$1") (pin "P8.43") (pinfunction "GPIO_72_P8.43") (pintype "bidirectional"))
    )
    (net (code "71") (name "unconnected-(U$1A-GPIO_73-PadP8.44)") (class "Default")
      (node (ref "U$1") (pin "P8.44") (pinfunction "GPIO_73_P8.44") (pintype "bidirectional"))
    )
    (net (code "72") (name "unconnected-(U$1A-GPIO_74-PadP8.41)") (class "Default")
      (node (ref "U$1") (pin "P8.41") (pinfunction "GPIO_74_P8.41") (pintype "bidirectional"))
    )
    (net (code "73") (name "unconnected-(U$1A-GPIO_75-PadP8.42)") (class "Default")
      (node (ref "U$1") (pin "P8.42") (pinfunction "GPIO_75_P8.42") (pintype "bidirectional"))
    )
    (net (code "74") (name "unconnected-(U$1A-GPIO_76-PadP8.39)") (class "Default")
      (node (ref "U$1") (pin "P8.39") (pinfunction "GPIO_76_P8.39") (pintype "bidirectional"))
    )
    (net (code "75") (name "unconnected-(U$1A-GPIO_77-PadP8.40)") (class "Default")
      (node (ref "U$1") (pin "P8.40") (pinfunction "GPIO_77_P8.40") (pintype "bidirectional"))
    )
    (net (code "76") (name "unconnected-(U$1A-GPIO_78-PadP8.37)") (class "Default")
      (node (ref "U$1") (pin "P8.37") (pinfunction "GPIO_78_P8.37") (pintype "bidirectional"))
    )
    (net (code "77") (name "unconnected-(U$1A-GPIO_79-PadP8.38)") (class "Default")
      (node (ref "U$1") (pin "P8.38") (pinfunction "GPIO_79_P8.38") (pintype "bidirectional"))
    )
    (net (code "78") (name "unconnected-(U$1A-GPIO_80-PadP8.36)") (class "Default")
      (node (ref "U$1") (pin "P8.36") (pinfunction "GPIO_80_P8.36") (pintype "bidirectional"))
    )
    (net (code "79") (name "unconnected-(U$1A-GPIO_81-PadP8.34)") (class "Default")
      (node (ref "U$1") (pin "P8.34") (pinfunction "GPIO_81_P8.34") (pintype "bidirectional"))
    )
    (net (code "80") (name "unconnected-(U$1A-GPIO_86-PadP8.27)") (class "Default")
      (node (ref "U$1") (pin "P8.27") (pinfunction "GPIO_86_P8.27") (pintype "bidirectional"))
    )
    (net (code "81") (name "unconnected-(U$1A-GPIO_87-PadP8.29)") (class "Default")
      (node (ref "U$1") (pin "P8.29") (pinfunction "GPIO_87_P8.29") (pintype "bidirectional"))
    )
    (net (code "82") (name "unconnected-(U$1A-GPIO_88-PadP8.28)") (class "Default")
      (node (ref "U$1") (pin "P8.28") (pinfunction "GPIO_88_P8.28") (pintype "bidirectional"))
    )
    (net (code "83") (name "unconnected-(U$1A-GPIO_89-PadP8.30)") (class "Default")
      (node (ref "U$1") (pin "P8.30") (pinfunction "GPIO_89_P8.30") (pintype "bidirectional"))
    )
    (net (code "84") (name "unconnected-(U$1B-AIN0-PadP9.39)") (class "Default")
      (node (ref "U$1") (pin "P9.39") (pinfunction "AIN0_P9.39") (pintype "bidirectional"))
    )
    (net (code "85") (name "unconnected-(U$1B-AIN1-PadP9.40)") (class "Default")
      (node (ref "U$1") (pin "P9.40") (pinfunction "AIN1_P9.40") (pintype "bidirectional"))
    )
    (net (code "86") (name "unconnected-(U$1B-AIN2-PadP9.37)") (class "Default")
      (node (ref "U$1") (pin "P9.37") (pinfunction "AIN2_P9.37") (pintype "bidirectional"))
    )
    (net (code "87") (name "unconnected-(U$1B-AIN3-PadP9.38)") (class "Default")
      (node (ref "U$1") (pin "P9.38") (pinfunction "AIN3_P9.38") (pintype "bidirectional"))
    )
    (net (code "88") (name "unconnected-(U$1B-AIN4-PadP9.33)") (class "Default")
      (node (ref "U$1") (pin "P9.33") (pinfunction "AIN4_P9.33") (pintype "bidirectional"))
    )
    (net (code "89") (name "unconnected-(U$1B-AIN5-PadP9.36)") (class "Default")
      (node (ref "U$1") (pin "P9.36") (pinfunction "AIN5_P9.36") (pintype "bidirectional"))
    )
    (net (code "90") (name "unconnected-(U$1B-AIN6-PadP9.35)") (class "Default")
      (node (ref "U$1") (pin "P9.35") (pinfunction "AIN6_P9.35") (pintype "bidirectional"))
    )
    (net (code "91") (name "unconnected-(U$1B-GNDA_ADC-PadP9.34)") (class "Default")
      (node (ref "U$1") (pin "P9.34") (pinfunction "GNDA_ADC_P9.34") (pintype "bidirectional"))
    )
    (net (code "92") (name "unconnected-(U$1B-GPIO_2-PadP9.22)") (class "Default")
      (node (ref "U$1") (pin "P9.22") (pinfunction "GPIO_2_P9.22") (pintype "bidirectional"))
    )
    (net (code "93") (name "unconnected-(U$1B-GPIO_3-PadP9.21)") (class "Default")
      (node (ref "U$1") (pin "P9.21") (pinfunction "GPIO_3_P9.21") (pintype "bidirectional"))
    )
    (net (code "94") (name "unconnected-(U$1B-GPIO_4-PadP9.17)") (class "Default")
      (node (ref "U$1") (pin "P9.17") (pinfunction "GPIO_4_P9.17") (pintype "bidirectional"))
    )
    (net (code "95") (name "unconnected-(U$1B-GPIO_5-PadP9.18)") (class "Default")
      (node (ref "U$1") (pin "P9.18") (pinfunction "GPIO_5_P9.18") (pintype "bidirectional"))
    )
    (net (code "96") (name "unconnected-(U$1B-GPIO_7-PadP9.42)") (class "Default")
      (node (ref "U$1") (pin "P9.42") (pinfunction "GPIO_7_P9.42") (pintype "bidirectional"))
    )
    (net (code "97") (name "unconnected-(U$1B-GPIO_14-PadP9.26)") (class "Default")
      (node (ref "U$1") (pin "P9.26") (pinfunction "GPIO_14_P9.26") (pintype "bidirectional"))
    )
    (net (code "98") (name "unconnected-(U$1B-GPIO_15-PadP9.24)") (class "Default")
      (node (ref "U$1") (pin "P9.24") (pinfunction "GPIO_15_P9.24") (pintype "bidirectional"))
    )
    (net (code "99") (name "unconnected-(U$1B-GPIO_20-PadP9.41)") (class "Default")
      (node (ref "U$1") (pin "P9.41") (pinfunction "GPIO_20_P9.41") (pintype "bidirectional"))
    )
    (net (code "100") (name "unconnected-(U$1B-GPIO_30-PadP9.11)") (class "Default")
      (node (ref "U$1") (pin "P9.11") (pinfunction "GPIO_30_P9.11") (pintype "bidirectional"))
    )
    (net (code "101") (name "unconnected-(U$1B-GPIO_31-PadP9.13)") (class "Default")
      (node (ref "U$1") (pin "P9.13") (pinfunction "GPIO_31_P9.13") (pintype "bidirectional"))
    )
    (net (code "102") (name "unconnected-(U$1B-GPIO_40-PadP9.14)") (class "Default")
      (node (ref "U$1") (pin "P9.14") (pinfunction "GPIO_40_P9.14") (pintype "bidirectional"))
    )
    (net (code "103") (name "unconnected-(U$1B-GPIO_48-PadP9.15)") (class "Default")
      (node (ref "U$1") (pin "P9.15") (pinfunction "GPIO_48_P9.15") (pintype "bidirectional"))
    )
    (net (code "104") (name "unconnected-(U$1B-GPIO_49-PadP9.23)") (class "Default")
      (node (ref "U$1") (pin "P9.23") (pinfunction "GPIO_49_P9.23") (pintype "bidirectional"))
    )
    (net (code "105") (name "unconnected-(U$1B-GPIO_51-PadP9.16)") (class "Default")
      (node (ref "U$1") (pin "P9.16") (pinfunction "GPIO_51_P9.16") (pintype "bidirectional"))
    )
    (net (code "106") (name "unconnected-(U$1B-GPIO_60-PadP9.12)") (class "Default")
      (node (ref "U$1") (pin "P9.12") (pinfunction "GPIO_60_P9.12") (pintype "bidirectional"))
    )
    (net (code "107") (name "unconnected-(U$1B-GPIO_117-PadP9.25)") (class "Default")
      (node (ref "U$1") (pin "P9.25") (pinfunction "GPIO_117_P9.25") (pintype "bidirectional"))
    )
    (net (code "108") (name "unconnected-(U$1B-GPIO_120-PadP9.31)") (class "Default")
      (node (ref "U$1") (pin "P9.31") (pinfunction "GPIO_120_P9.31") (pintype "bidirectional"))
    )
    (net (code "109") (name "unconnected-(U$1B-GPIO_121-PadP9.29)") (class "Default")
      (node (ref "U$1") (pin "P9.29") (pinfunction "GPIO_121_P9.29") (pintype "bidirectional"))
    )
    (net (code "110") (name "unconnected-(U$1B-GPIO_122-PadP9.30)") (class "Default")
      (node (ref "U$1") (pin "P9.30") (pinfunction "GPIO_122_P9.30") (pintype "bidirectional"))
    )
    (net (code "111") (name "unconnected-(U$1B-GPIO_123-PadP9.28)") (class "Default")
      (node (ref "U$1") (pin "P9.28") (pinfunction "GPIO_123_P9.28") (pintype "bidirectional"))
    )
    (net (code "112") (name "unconnected-(U$1B-GPIO_125-PadP9.27)") (class "Default")
      (node (ref "U$1") (pin "P9.27") (pinfunction "GPIO_125_P9.27") (pintype "bidirectional"))
    )
    (net (code "113") (name "unconnected-(U$1B-PWR_BUT-PadP9.9)") (class "Default")
      (node (ref "U$1") (pin "P9.9") (pinfunction "PWR_BUT_P9.9") (pintype "bidirectional"))
    )
    (net (code "114") (name "unconnected-(U$1B-SYS_5V-PadP9.7)") (class "Default")
      (node (ref "U$1") (pin "P9.7") (pinfunction "SYS_5V_P9.7") (pintype "bidirectional"))
    )
    (net (code "115") (name "unconnected-(U$1B-SYS_5V-PadP9.8)") (class "Default")
      (node (ref "U$1") (pin "P9.8") (pinfunction "SYS_5V_P9.8") (pintype "bidirectional"))
    )
    (net (code "116") (name "unconnected-(U$1B-SYS_RESET~{N}-PadP9.10)") (class "Default")
      (node (ref "U$1") (pin "P9.10") (pinfunction "SYS_RESET~{N}_P9.10") (pintype "bidirectional"))
    )
    (net (code "117") (name "unconnected-(U$1B-VDD_3V3-PadP9.3)") (class "Default")
      (node (ref "U$1") (pin "P9.3") (pinfunction "VDD_3V3_P9.3") (pintype "bidirectional"))
    )
    (net (code "118") (name "unconnected-(U$1B-VDD_3V3-PadP9.4)") (class "Default")
      (node (ref "U$1") (pin "P9.4") (pinfunction "VDD_3V3_P9.4") (pintype "bidirectional"))
    )
    (net (code "119") (name "unconnected-(U$1B-VDD_5V-PadP9.5)") (class "Default")
      (node (ref "U$1") (pin "P9.5") (pinfunction "VDD_5V_P9.5") (pintype "bidirectional"))
    )
    (net (code "120") (name "unconnected-(U$1B-VDD_5V-PadP9.6)") (class "Default")
      (node (ref "U$1") (pin "P9.6") (pinfunction "VDD_5V_P9.6") (pintype "bidirectional"))
    )
    (net (code "121") (name "unconnected-(U$1B-VDD_ADC-PadP9.32)") (class "Default")
      (node (ref "U$1") (pin "P9.32") (pinfunction "VDD_ADC_P9.32") (pintype "bidirectional"))
    )
    (net (code "122") (name "unconnected-(U$12-Pad6)") (class "Default")
      (node (ref "U$12") (pin "6") (pinfunction "6_6") (pintype "passive"))
    )
    (net (code "123") (name "unconnected-(U$12-Pad10)") (class "Default")
      (node (ref "U$12") (pin "10") (pinfunction "10_10") (pintype "passive"))
    )
    (net (code "124") (name "unconnected-(U$12-Pad12)") (class "Default")
      (node (ref "U$12") (pin "12") (pinfunction "12_12") (pintype "passive"))
    )
    (net (code "125") (name "unconnected-(U$12-Pad13)") (class "Default")
      (node (ref "U$12") (pin "13") (pinfunction "13_13") (pintype "passive"))
    )
    (net (code "126") (name "unconnected-(U$12-Pad14)") (class "Default")
      (node (ref "U$12") (pin "14") (pinfunction "14_14") (pintype "passive"))
    )
    (net (code "127") (name "unconnected-(U5-OUT-Pad2)") (class "Default")
      (node (ref "U5") (pin "2") (pinfunction "OUT_2") (pintype "output"))
    )
    (net (code "128") (name "unconnected-(U6-P2.0-Pad23)") (class "Default")
      (node (ref "U6") (pin "23") (pinfunction "P2.0_23") (pintype "bidirectional"))
    )
    (net (code "129") (name "unconnected-(U6-P2.3-Pad36)") (class "Default")
      (node (ref "U6") (pin "36") (pinfunction "P2.3_36") (pintype "bidirectional"))
    )
    (net (code "130") (name "unconnected-(U6-P2.4-Pad37)") (class "Default")
      (node (ref "U6") (pin "37") (pinfunction "P2.4_37") (pintype "bidirectional"))
    )
    (net (code "131") (name "unconnected-(U6-P2.5-Pad19)") (class "Default")
      (node (ref "U6") (pin "19") (pinfunction "P2.5_19") (pintype "bidirectional"))
    )
    (net (code "132") (name "unconnected-(U6-P2.6-Pad20)") (class "Default")
      (node (ref "U6") (pin "20") (pinfunction "P2.6_20") (pintype "bidirectional"))
    )
    (net (code "133") (name "unconnected-(U6-P2.7-Pad35)") (class "Default")
      (node (ref "U6") (pin "35") (pinfunction "P2.7_35") (pintype "bidirectional"))
    )
    (net (code "134") (name "unconnected-(U6-P3.2-Pad10)") (class "Default")
      (node (ref "U6") (pin "10") (pinfunction "P3.2_10") (pintype "bidirectional"))
    )
    (net (code "135") (name "unconnected-(U6-P3.3-Pad11)") (class "Default")
      (node (ref "U6") (pin "11") (pinfunction "P3.3_11") (pintype "bidirectional"))
    )
    (net (code "136") (name "unconnected-(U6-P3.6-Pad28)") (class "Default")
      (node (ref "U6") (pin "28") (pinfunction "P3.6_28") (pintype "bidirectional"))
    )
    (net (code "137") (name "unconnected-(U6-P3.7-Pad29)") (class "Default")
      (node (ref "U6") (pin "29") (pinfunction "P3.7_29") (pintype "bidirectional"))
    )
    (net (code "138") (name "unconnected-(U6-PJ.4{slash}XIN-Pad1)") (class "Default")
      (node (ref "U6") (pin "1") (pinfunction "PJ.4/XIN_1") (pintype "bidirectional"))
    )
    (net (code "139") (name "unconnected-(U6-PJ.5{slash}XOUT-Pad2)") (class "Default")
      (node (ref "U6") (pin "2") (pinfunction "PJ.5/XOUT_2") (pintype "bidirectional"))
    )
  )
)
